# HF_LPF.net
KiCad netlist of a schematic drawn in Altium Designer
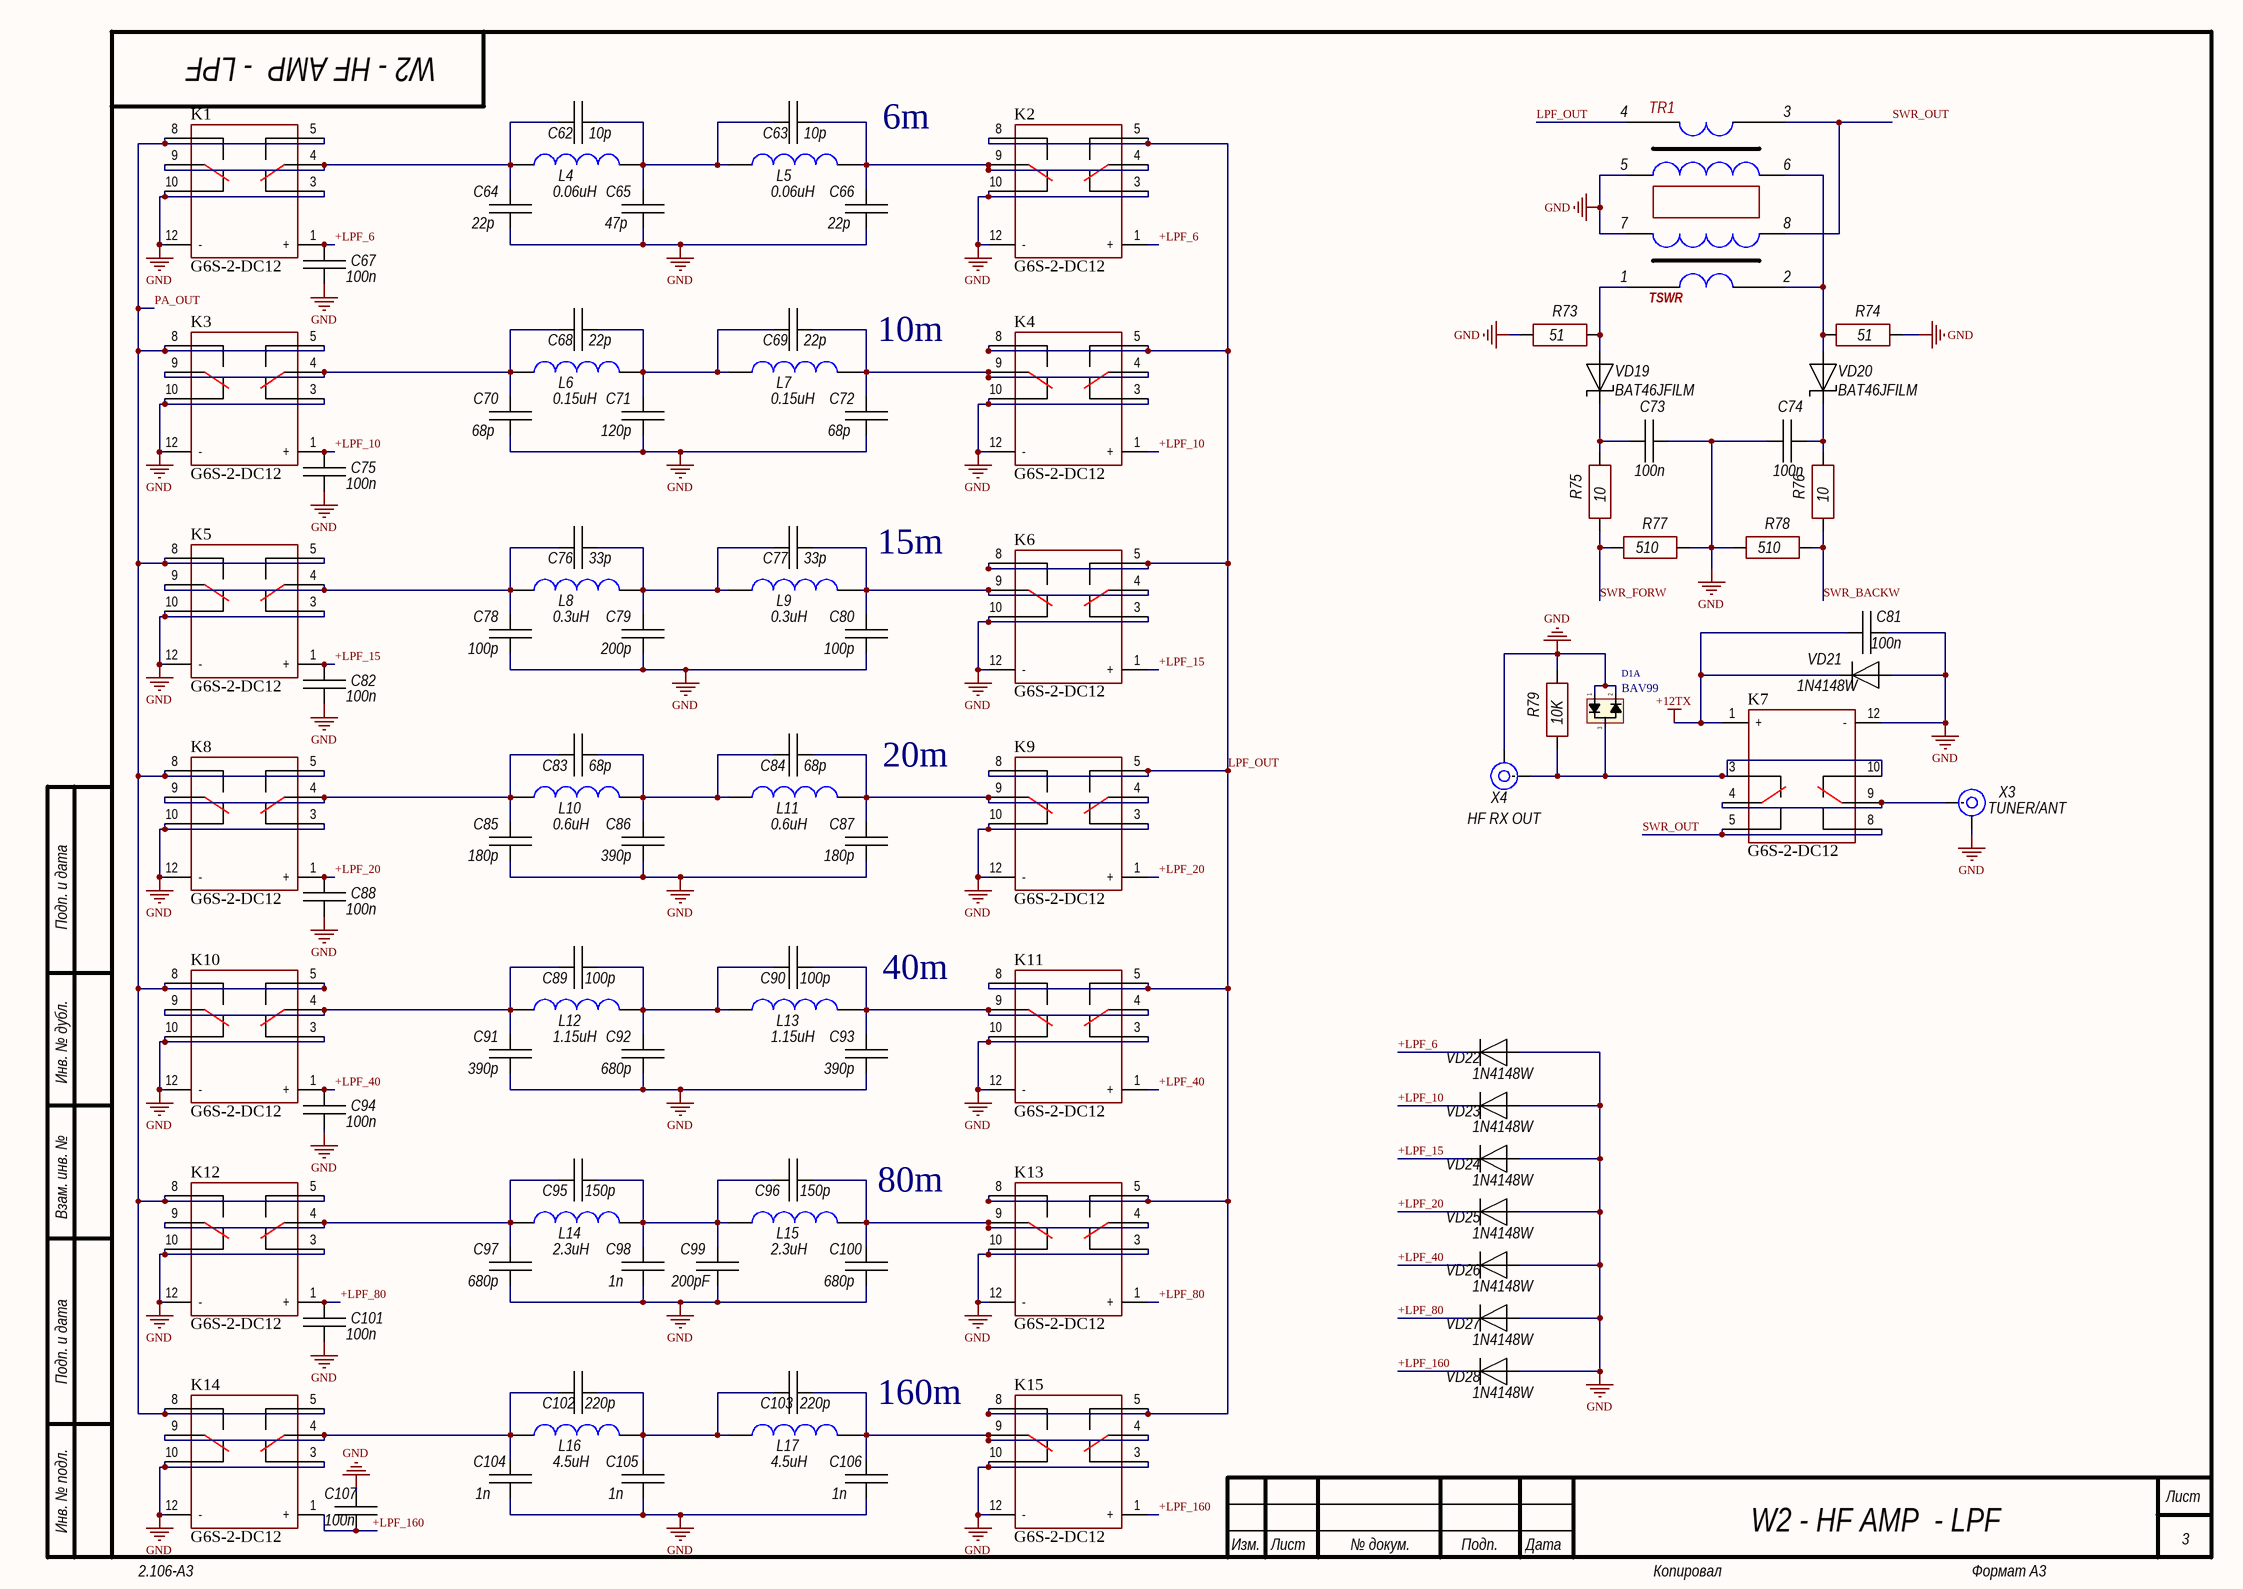
[diagram p0: HF_LPF.SchDoc]

(export (version "E")
  (design (tool "Eeschema 10.0.6"))
  (components
    (comp (ref "C62") (value "10p") (footprint "CH1206ATC") (libsource (lib "Discrete") (part "Capacitor")))
    (comp (ref "C63") (value "10p") (footprint "CH1206ATC") (libsource (lib "Discrete") (part "Capacitor")))
    (comp (ref "C64") (value "22p") (footprint "CH1206ATC") (libsource (lib "Discrete") (part "Capacitor")))
    (comp (ref "C65") (value "47p") (footprint "CH1206ATC") (libsource (lib "Discrete") (part "Capacitor")))
    (comp (ref "C66") (value "22p") (footprint "CH1206ATC") (libsource (lib "Discrete") (part "Capacitor")))
    (comp (ref "C67")
      (value "100n")
      (footprint "standard:CH0805C")
      (libsource (lib "Discrete") (part "Capacitor"))
    )
    (comp (ref "C68") (value "22p") (footprint "CH1206ATC") (libsource (lib "Discrete") (part "Capacitor")))
    (comp (ref "C69") (value "22p") (footprint "CH1206ATC") (libsource (lib "Discrete") (part "Capacitor")))
    (comp (ref "C70") (value "68p") (footprint "CH1206ATC") (libsource (lib "Discrete") (part "Capacitor")))
    (comp (ref "C71") (value "120p") (footprint "CH1206ATC") (libsource (lib "Discrete") (part "Capacitor")))
    (comp (ref "C72") (value "68p") (footprint "CH1206ATC") (libsource (lib "Discrete") (part "Capacitor")))
    (comp (ref "C73")
      (value "100n")
      (footprint "standard:CH1206C")
      (libsource (lib "Discrete") (part "Capacitor"))
    )
    (comp (ref "C74")
      (value "100n")
      (footprint "standard:CH1206C")
      (libsource (lib "Discrete") (part "Capacitor"))
    )
    (comp (ref "C75")
      (value "100n")
      (footprint "standard:CH0805C")
      (libsource (lib "Discrete") (part "Capacitor"))
    )
    (comp (ref "C76") (value "33p") (footprint "CH1206ATC") (libsource (lib "Discrete") (part "Capacitor")))
    (comp (ref "C77") (value "33p") (footprint "CH1206ATC") (libsource (lib "Discrete") (part "Capacitor")))
    (comp (ref "C78") (value "100p") (footprint "CH1206ATC") (libsource (lib "Discrete") (part "Capacitor")))
    (comp (ref "C79") (value "200p") (footprint "CH1206ATC") (libsource (lib "Discrete") (part "Capacitor")))
    (comp (ref "C80") (value "100p") (footprint "CH1206ATC") (libsource (lib "Discrete") (part "Capacitor")))
    (comp (ref "C81")
      (value "100n")
      (footprint "standard:CH1206C")
      (libsource (lib "Discrete") (part "Capacitor"))
    )
    (comp (ref "C82")
      (value "100n")
      (footprint "standard:CH0805C")
      (libsource (lib "Discrete") (part "Capacitor"))
    )
    (comp (ref "C83") (value "68p") (footprint "CH1206ATC") (libsource (lib "Discrete") (part "Capacitor")))
    (comp (ref "C84") (value "68p") (footprint "CH1206ATC") (libsource (lib "Discrete") (part "Capacitor")))
    (comp (ref "C85") (value "180p") (footprint "CH1206ATC") (libsource (lib "Discrete") (part "Capacitor")))
    (comp (ref "C86") (value "390p") (footprint "CH1206ATC") (libsource (lib "Discrete") (part "Capacitor")))
    (comp (ref "C87") (value "180p") (footprint "CH1206ATC") (libsource (lib "Discrete") (part "Capacitor")))
    (comp (ref "C88")
      (value "100n")
      (footprint "standard:CH0805C")
      (libsource (lib "Discrete") (part "Capacitor"))
    )
    (comp (ref "C89") (value "100p") (footprint "CH1206ATC") (libsource (lib "Discrete") (part "Capacitor")))
    (comp (ref "C90") (value "100p") (footprint "CH1206ATC") (libsource (lib "Discrete") (part "Capacitor")))
    (comp (ref "C91") (value "390p") (footprint "CH1206ATC") (libsource (lib "Discrete") (part "Capacitor")))
    (comp (ref "C92") (value "680p") (footprint "CH1206ATC") (libsource (lib "Discrete") (part "Capacitor")))
    (comp (ref "C93") (value "390p") (footprint "CH1206ATC") (libsource (lib "Discrete") (part "Capacitor")))
    (comp (ref "C94")
      (value "100n")
      (footprint "standard:CH0805C")
      (libsource (lib "Discrete") (part "Capacitor"))
    )
    (comp (ref "C95") (value "150p") (footprint "CH1206ATC") (libsource (lib "Discrete") (part "Capacitor")))
    (comp (ref "C96") (value "150p") (footprint "CH1206ATC") (libsource (lib "Discrete") (part "Capacitor")))
    (comp (ref "C97") (value "680p") (footprint "CH1206ATC") (libsource (lib "Discrete") (part "Capacitor")))
    (comp (ref "C98") (value "1n") (footprint "CH1206ATC") (libsource (lib "Discrete") (part "Capacitor")))
    (comp (ref "C99") (value "200pF") (footprint "CH1206ATC") (libsource (lib "Discrete") (part "Capacitor")))
    (comp (ref "C100") (value "680p") (footprint "CH1206ATC") (libsource (lib "Discrete") (part "Capacitor")))
    (comp (ref "C101")
      (value "100n")
      (footprint "standard:CH0805C")
      (libsource (lib "Discrete") (part "Capacitor"))
    )
    (comp (ref "C102") (value "220p") (footprint "CH1206ATC") (libsource (lib "Discrete") (part "Capacitor")))
    (comp (ref "C103") (value "220p") (footprint "CH1206ATC") (libsource (lib "Discrete") (part "Capacitor")))
    (comp (ref "C104") (value "1n") (footprint "CH1206ATC") (libsource (lib "Discrete") (part "Capacitor")))
    (comp (ref "C105") (value "1n") (footprint "CH1206ATC") (libsource (lib "Discrete") (part "Capacitor")))
    (comp (ref "C106") (value "1n") (footprint "CH1206ATC") (libsource (lib "Discrete") (part "Capacitor")))
    (comp (ref "C107")
      (value "100n")
      (footprint "standard:CH0805C")
      (libsource (lib "Discrete") (part "Capacitor"))
    )
    (comp (ref "D1") (value "BAV99") (footprint "SOT23_132") (libsource (lib "Analog") (part "BAV99")))
    (comp (ref "K1")
      (value "G6S-2-DC12")
      (footprint "G6S-2-DC12")
      (libsource (lib "Relay") (part "G6S-2-DC12V_2"))
    )
    (comp (ref "K2")
      (value "G6S-2-DC12")
      (footprint "G6S-2-DC12")
      (libsource (lib "Relay") (part "G6S-2-DC12V_2"))
    )
    (comp (ref "K3")
      (value "G6S-2-DC12")
      (footprint "G6S-2-DC12")
      (libsource (lib "Relay") (part "G6S-2-DC12V_2"))
    )
    (comp (ref "K4")
      (value "G6S-2-DC12")
      (footprint "G6S-2-DC12")
      (libsource (lib "Relay") (part "G6S-2-DC12V_2"))
    )
    (comp (ref "K5")
      (value "G6S-2-DC12")
      (footprint "G6S-2-DC12")
      (libsource (lib "Relay") (part "G6S-2-DC12V_2"))
    )
    (comp (ref "K6")
      (value "G6S-2-DC12")
      (footprint "G6S-2-DC12")
      (libsource (lib "Relay") (part "G6S-2-DC12V_2"))
    )
    (comp (ref "K7")
      (value "G6S-2-DC12")
      (footprint "G6S-2-DC12")
      (libsource (lib "") (part "G6S-2-DC12V_2_1"))
    )
    (comp (ref "K8")
      (value "G6S-2-DC12")
      (footprint "G6S-2-DC12")
      (libsource (lib "Relay") (part "G6S-2-DC12V_2"))
    )
    (comp (ref "K9")
      (value "G6S-2-DC12")
      (footprint "G6S-2-DC12")
      (libsource (lib "Relay") (part "G6S-2-DC12V_2"))
    )
    (comp (ref "K10")
      (value "G6S-2-DC12")
      (footprint "G6S-2-DC12")
      (libsource (lib "Relay") (part "G6S-2-DC12V_2"))
    )
    (comp (ref "K11")
      (value "G6S-2-DC12")
      (footprint "G6S-2-DC12")
      (libsource (lib "Relay") (part "G6S-2-DC12V_2"))
    )
    (comp (ref "K12")
      (value "G6S-2-DC12")
      (footprint "G6S-2-DC12")
      (libsource (lib "Relay") (part "G6S-2-DC12V_2"))
    )
    (comp (ref "K13")
      (value "G6S-2-DC12")
      (footprint "G6S-2-DC12")
      (libsource (lib "Relay") (part "G6S-2-DC12V_2"))
    )
    (comp (ref "K14")
      (value "G6S-2-DC12")
      (footprint "G6S-2-DC12")
      (libsource (lib "Relay") (part "G6S-2-DC12V_2"))
    )
    (comp (ref "K15")
      (value "G6S-2-DC12")
      (footprint "G6S-2-DC12")
      (libsource (lib "Relay") (part "G6S-2-DC12V_2"))
    )
    (comp (ref "L4")
      (value "0.06uH")
      (footprint "DR1")
      (libsource (lib "Transformers") (part "Inductor ring"))
    )
    (comp (ref "L5")
      (value "0.06uH")
      (footprint "DR1")
      (libsource (lib "Transformers") (part "Inductor ring"))
    )
    (comp (ref "L6")
      (value "0.15uH")
      (footprint "DR1")
      (libsource (lib "Transformers") (part "Inductor ring"))
    )
    (comp (ref "L7")
      (value "0.15uH")
      (footprint "DR1")
      (libsource (lib "Transformers") (part "Inductor ring"))
    )
    (comp (ref "L8")
      (value "0.3uH")
      (footprint "T68-0")
      (libsource (lib "Transformers") (part "Inductor ring"))
    )
    (comp (ref "L9")
      (value "0.3uH")
      (footprint "T68-0")
      (libsource (lib "Transformers") (part "Inductor ring"))
    )
    (comp (ref "L10")
      (value "0.6uH")
      (footprint "T68-0")
      (libsource (lib "Transformers") (part "Inductor ring"))
    )
    (comp (ref "L11")
      (value "0.6uH")
      (footprint "T68-0")
      (libsource (lib "Transformers") (part "Inductor ring"))
    )
    (comp (ref "L12")
      (value "1.15uH")
      (footprint "T68-0")
      (libsource (lib "Transformers") (part "Inductor ring"))
    )
    (comp (ref "L13")
      (value "1.15uH")
      (footprint "T68-0")
      (libsource (lib "Transformers") (part "Inductor ring"))
    )
    (comp (ref "L14")
      (value "2.3uH")
      (footprint "T68-0")
      (libsource (lib "Transformers") (part "Inductor ring"))
    )
    (comp (ref "L15")
      (value "2.3uH")
      (footprint "T68-0")
      (libsource (lib "Transformers") (part "Inductor ring"))
    )
    (comp (ref "L16")
      (value "4.5uH")
      (footprint "T68-0")
      (libsource (lib "Transformers") (part "Inductor ring"))
    )
    (comp (ref "L17")
      (value "4.5uH")
      (footprint "T68-0")
      (libsource (lib "Transformers") (part "Inductor ring"))
    )
    (comp (ref "R73")
      (value "51")
      (footprint "standard:CH1206R")
      (libsource (lib "Discrete") (part "Resistor"))
    )
    (comp (ref "R74")
      (value "51")
      (footprint "standard:CH1206R")
      (libsource (lib "Discrete") (part "Resistor"))
    )
    (comp (ref "R75") (value "10") (footprint "standard:CH0805R") (libsource (lib "") (part "Resistor_1")))
    (comp (ref "R76") (value "10") (footprint "standard:CH0805R") (libsource (lib "") (part "Resistor_1")))
    (comp (ref "R77")
      (value "510")
      (footprint "standard:CH0805R")
      (libsource (lib "Discrete") (part "Resistor"))
    )
    (comp (ref "R78")
      (value "510")
      (footprint "standard:CH0805R")
      (libsource (lib "Discrete") (part "Resistor"))
    )
    (comp (ref "R79") (value "10K") (footprint "standard:CH2512R") (libsource (lib "") (part "Resistor_1")))
    (comp (ref "TR1") (value "TSWR") (footprint "TANDEM") (libsource (lib "Transformers") (part "BN43-302")))
    (comp (ref "VD19")
      (value "BAT46JFILM")
      (footprint "standard:SOD323")
      (libsource (lib "Diods") (part "Diod Schottky"))
    )
    (comp (ref "VD20")
      (value "BAT46JFILM")
      (footprint "standard:SOD323")
      (libsource (lib "Diods") (part "Diod Schottky"))
    )
    (comp (ref "VD21")
      (value "1N4148W")
      (footprint "standard:SOD123")
      (libsource (lib "Diods") (part "Diod"))
    )
    (comp (ref "VD22")
      (value "1N4148W")
      (footprint "standard:SOD123")
      (libsource (lib "Diods") (part "Diod"))
    )
    (comp (ref "VD23")
      (value "1N4148W")
      (footprint "standard:SOD123")
      (libsource (lib "Diods") (part "Diod"))
    )
    (comp (ref "VD24")
      (value "1N4148W")
      (footprint "standard:SOD123")
      (libsource (lib "Diods") (part "Diod"))
    )
    (comp (ref "VD25")
      (value "1N4148W")
      (footprint "standard:SOD123")
      (libsource (lib "Diods") (part "Diod"))
    )
    (comp (ref "VD26")
      (value "1N4148W")
      (footprint "standard:SOD123")
      (libsource (lib "Diods") (part "Diod"))
    )
    (comp (ref "VD27")
      (value "1N4148W")
      (footprint "standard:SOD123")
      (libsource (lib "Diods") (part "Diod"))
    )
    (comp (ref "VD28")
      (value "1N4148W")
      (footprint "standard:SOD123")
      (libsource (lib "Diods") (part "Diod"))
    )
    (comp (ref "X3")
      (value "TUNER/ANT")
      (footprint "custom:CON: SMA")
      (description "RF")
      (libsource (lib "Connectors") (part "SMA"))
    )
    (comp (ref "X4")
      (value "HF RX OUT")
      (footprint "custom:CON: SMA")
      (description "RF")
      (libsource (lib "Connectors") (part "SMA"))
    )
  )
  (nets
    (net (code "1") (name "+12TX") (class "Default")
      (node (ref "C81") (pin "1") (pinfunction "1_1") (pintype "power_in"))
      (node (ref "K7") (pin "1") (pinfunction "+_1") (pintype "passive"))
      (node (ref "VD21") (pin "2") (pinfunction "2_2") (pintype "passive"))
    )
    (net (code "2") (name "/+LPF_6") (class "Default")
      (node (ref "C67") (pin "1") (pinfunction "1_1") (pintype "power_in"))
      (node (ref "K1") (pin "1") (pinfunction "+_1") (pintype "passive"))
      (node (ref "K2") (pin "1") (pinfunction "+_1") (pintype "passive"))
      (node (ref "VD22") (pin "2") (pinfunction "2_2") (pintype "passive"))
    )
    (net (code "3") (name "/+LPF_10") (class "Default")
      (node (ref "C75") (pin "1") (pinfunction "1_1") (pintype "power_in"))
      (node (ref "K3") (pin "1") (pinfunction "+_1") (pintype "passive"))
      (node (ref "K4") (pin "1") (pinfunction "+_1") (pintype "passive"))
      (node (ref "VD23") (pin "2") (pinfunction "2_2") (pintype "passive"))
    )
    (net (code "4") (name "/+LPF_15") (class "Default")
      (node (ref "C82") (pin "1") (pinfunction "1_1") (pintype "power_in"))
      (node (ref "K5") (pin "1") (pinfunction "+_1") (pintype "passive"))
      (node (ref "K6") (pin "1") (pinfunction "+_1") (pintype "passive"))
      (node (ref "VD24") (pin "2") (pinfunction "2_2") (pintype "passive"))
    )
    (net (code "5") (name "/+LPF_20") (class "Default")
      (node (ref "C88") (pin "1") (pinfunction "1_1") (pintype "power_in"))
      (node (ref "K8") (pin "1") (pinfunction "+_1") (pintype "passive"))
      (node (ref "K9") (pin "1") (pinfunction "+_1") (pintype "passive"))
      (node (ref "VD25") (pin "2") (pinfunction "2_2") (pintype "passive"))
    )
    (net (code "6") (name "/+LPF_40") (class "Default")
      (node (ref "C94") (pin "1") (pinfunction "1_1") (pintype "power_in"))
      (node (ref "K10") (pin "1") (pinfunction "+_1") (pintype "passive"))
      (node (ref "K11") (pin "1") (pinfunction "+_1") (pintype "passive"))
      (node (ref "VD26") (pin "2") (pinfunction "2_2") (pintype "passive"))
    )
    (net (code "7") (name "/+LPF_80") (class "Default")
      (node (ref "C101") (pin "1") (pinfunction "1_1") (pintype "power_in"))
      (node (ref "K12") (pin "1") (pinfunction "+_1") (pintype "passive"))
      (node (ref "K13") (pin "1") (pinfunction "+_1") (pintype "passive"))
      (node (ref "VD27") (pin "2") (pinfunction "2_2") (pintype "passive"))
    )
    (net (code "8") (name "/+LPF_160") (class "Default")
      (node (ref "C107") (pin "2") (pinfunction "2_2") (pintype "power_in"))
      (node (ref "K14") (pin "1") (pinfunction "+_1") (pintype "passive"))
      (node (ref "K15") (pin "1") (pinfunction "+_1") (pintype "passive"))
      (node (ref "VD28") (pin "2") (pinfunction "2_2") (pintype "passive"))
    )
    (net (code "9") (name "/LPF_OUT") (class "Default")
      (node (ref "K11") (pin "5") (pinfunction "NO_1_5") (pintype "passive"))
      (node (ref "K11") (pin "8") (pinfunction "NO_2_8") (pintype "passive"))
      (node (ref "K13") (pin "5") (pinfunction "NO_1_5") (pintype "passive"))
      (node (ref "K13") (pin "8") (pinfunction "NO_2_8") (pintype "passive"))
      (node (ref "K15") (pin "5") (pinfunction "NO_1_5") (pintype "passive"))
      (node (ref "K15") (pin "8") (pinfunction "NO_2_8") (pintype "passive"))
      (node (ref "K2") (pin "5") (pinfunction "NO_1_5") (pintype "passive"))
      (node (ref "K2") (pin "8") (pinfunction "NO_2_8") (pintype "passive"))
      (node (ref "K4") (pin "5") (pinfunction "NO_1_5") (pintype "passive"))
      (node (ref "K4") (pin "8") (pinfunction "NO_2_8") (pintype "passive"))
      (node (ref "K6") (pin "5") (pinfunction "NO_1_5") (pintype "passive"))
      (node (ref "K6") (pin "8") (pinfunction "NO_2_8") (pintype "passive"))
      (node (ref "K9") (pin "5") (pinfunction "NO_1_5") (pintype "passive"))
      (node (ref "K9") (pin "8") (pinfunction "NO_2_8") (pintype "passive"))
      (node (ref "TR1") (pin "4") (pinfunction "4_4") (pintype "power_in"))
    )
    (net (code "10") (name "/PA_OUT") (class "Default")
      (node (ref "K1") (pin "5") (pinfunction "NO_1_5") (pintype "passive"))
      (node (ref "K1") (pin "8") (pinfunction "NO_2_8") (pintype "passive"))
      (node (ref "K10") (pin "5") (pinfunction "NO_1_5") (pintype "passive"))
      (node (ref "K10") (pin "8") (pinfunction "NO_2_8") (pintype "passive"))
      (node (ref "K12") (pin "5") (pinfunction "NO_1_5") (pintype "passive"))
      (node (ref "K12") (pin "8") (pinfunction "NO_2_8") (pintype "passive"))
      (node (ref "K14") (pin "5") (pinfunction "NO_1_5") (pintype "passive"))
      (node (ref "K14") (pin "8") (pinfunction "NO_2_8") (pintype "passive"))
      (node (ref "K3") (pin "5") (pinfunction "NO_1_5") (pintype "passive"))
      (node (ref "K3") (pin "8") (pinfunction "NO_2_8") (pintype "passive"))
      (node (ref "K5") (pin "5") (pinfunction "NO_1_5") (pintype "passive"))
      (node (ref "K5") (pin "8") (pinfunction "NO_2_8") (pintype "passive"))
      (node (ref "K8") (pin "5") (pinfunction "NO_1_5") (pintype "passive"))
      (node (ref "K8") (pin "8") (pinfunction "NO_2_8") (pintype "passive"))
    )
    (net (code "11") (name "/SWR_BACKW") (class "Default")
      (node (ref "R76") (pin "1") (pinfunction "1_1") (pintype "passive"))
      (node (ref "R78") (pin "2") (pinfunction "2_2") (pintype "passive"))
    )
    (net (code "12") (name "/SWR_FORW") (class "Default")
      (node (ref "R75") (pin "1") (pinfunction "1_1") (pintype "passive"))
      (node (ref "R77") (pin "1") (pinfunction "1_1") (pintype "passive"))
    )
    (net (code "13") (name "/SWR_OUT") (class "Default")
      (node (ref "K7") (pin "5") (pinfunction "NO_1_5") (pintype "passive"))
      (node (ref "K7") (pin "8") (pinfunction "NO_2_8") (pintype "passive"))
      (node (ref "TR1") (pin "3") (pinfunction "3_3") (pintype "power_in"))
      (node (ref "TR1") (pin "8") (pinfunction "8_8") (pintype "power_in"))
    )
    (net (code "14") (name "GND") (class "Default")
      (node (ref "C100") (pin "1") (pinfunction "1_1") (pintype "power_in"))
      (node (ref "C101") (pin "2") (pinfunction "2_2") (pintype "power_in"))
      (node (ref "C104") (pin "1") (pinfunction "1_1") (pintype "power_in"))
      (node (ref "C105") (pin "1") (pinfunction "1_1") (pintype "power_in"))
      (node (ref "C106") (pin "1") (pinfunction "1_1") (pintype "power_in"))
      (node (ref "C107") (pin "1") (pinfunction "1_1") (pintype "power_in"))
      (node (ref "C64") (pin "1") (pinfunction "1_1") (pintype "power_in"))
      (node (ref "C65") (pin "1") (pinfunction "1_1") (pintype "power_in"))
      (node (ref "C66") (pin "1") (pinfunction "1_1") (pintype "power_in"))
      (node (ref "C67") (pin "2") (pinfunction "2_2") (pintype "power_in"))
      (node (ref "C70") (pin "1") (pinfunction "1_1") (pintype "power_in"))
      (node (ref "C71") (pin "1") (pinfunction "1_1") (pintype "power_in"))
      (node (ref "C72") (pin "1") (pinfunction "1_1") (pintype "power_in"))
      (node (ref "C73") (pin "2") (pinfunction "2_2") (pintype "power_in"))
      (node (ref "C74") (pin "1") (pinfunction "1_1") (pintype "power_in"))
      (node (ref "C75") (pin "2") (pinfunction "2_2") (pintype "power_in"))
      (node (ref "C78") (pin "1") (pinfunction "1_1") (pintype "power_in"))
      (node (ref "C79") (pin "1") (pinfunction "1_1") (pintype "power_in"))
      (node (ref "C80") (pin "1") (pinfunction "1_1") (pintype "power_in"))
      (node (ref "C81") (pin "2") (pinfunction "2_2") (pintype "power_in"))
      (node (ref "C82") (pin "2") (pinfunction "2_2") (pintype "power_in"))
      (node (ref "C85") (pin "1") (pinfunction "1_1") (pintype "power_in"))
      (node (ref "C86") (pin "1") (pinfunction "1_1") (pintype "power_in"))
      (node (ref "C87") (pin "1") (pinfunction "1_1") (pintype "power_in"))
      (node (ref "C88") (pin "2") (pinfunction "2_2") (pintype "power_in"))
      (node (ref "C91") (pin "1") (pinfunction "1_1") (pintype "power_in"))
      (node (ref "C92") (pin "1") (pinfunction "1_1") (pintype "power_in"))
      (node (ref "C93") (pin "1") (pinfunction "1_1") (pintype "power_in"))
      (node (ref "C94") (pin "2") (pinfunction "2_2") (pintype "power_in"))
      (node (ref "C97") (pin "1") (pinfunction "1_1") (pintype "power_in"))
      (node (ref "C98") (pin "1") (pinfunction "1_1") (pintype "power_in"))
      (node (ref "C99") (pin "1") (pinfunction "1_1") (pintype "power_in"))
      (node (ref "D1") (pin "1") (pinfunction "11_1") (pintype "passive"))
      (node (ref "D1") (pin "2") (pinfunction "10_2") (pintype "passive"))
      (node (ref "K1") (pin "10") (pinfunction "NC_2_10") (pintype "passive"))
      (node (ref "K1") (pin "12") (pinfunction "-_12") (pintype "passive"))
      (node (ref "K1") (pin "3") (pinfunction "NC_1_3") (pintype "passive"))
      (node (ref "K10") (pin "10") (pinfunction "NC_2_10") (pintype "passive"))
      (node (ref "K10") (pin "12") (pinfunction "-_12") (pintype "passive"))
      (node (ref "K10") (pin "3") (pinfunction "NC_1_3") (pintype "passive"))
      (node (ref "K11") (pin "10") (pinfunction "NC_2_10") (pintype "passive"))
      (node (ref "K11") (pin "12") (pinfunction "-_12") (pintype "passive"))
      (node (ref "K11") (pin "3") (pinfunction "NC_1_3") (pintype "passive"))
      (node (ref "K12") (pin "10") (pinfunction "NC_2_10") (pintype "passive"))
      (node (ref "K12") (pin "12") (pinfunction "-_12") (pintype "passive"))
      (node (ref "K12") (pin "3") (pinfunction "NC_1_3") (pintype "passive"))
      (node (ref "K13") (pin "10") (pinfunction "NC_2_10") (pintype "passive"))
      (node (ref "K13") (pin "12") (pinfunction "-_12") (pintype "passive"))
      (node (ref "K13") (pin "3") (pinfunction "NC_1_3") (pintype "passive"))
      (node (ref "K14") (pin "10") (pinfunction "NC_2_10") (pintype "passive"))
      (node (ref "K14") (pin "12") (pinfunction "-_12") (pintype "passive"))
      (node (ref "K14") (pin "3") (pinfunction "NC_1_3") (pintype "passive"))
      (node (ref "K15") (pin "10") (pinfunction "NC_2_10") (pintype "passive"))
      (node (ref "K15") (pin "12") (pinfunction "-_12") (pintype "passive"))
      (node (ref "K15") (pin "3") (pinfunction "NC_1_3") (pintype "passive"))
      (node (ref "K2") (pin "10") (pinfunction "NC_2_10") (pintype "passive"))
      (node (ref "K2") (pin "12") (pinfunction "-_12") (pintype "passive"))
      (node (ref "K2") (pin "3") (pinfunction "NC_1_3") (pintype "passive"))
      (node (ref "K3") (pin "10") (pinfunction "NC_2_10") (pintype "passive"))
      (node (ref "K3") (pin "12") (pinfunction "-_12") (pintype "passive"))
      (node (ref "K3") (pin "3") (pinfunction "NC_1_3") (pintype "passive"))
      (node (ref "K4") (pin "10") (pinfunction "NC_2_10") (pintype "passive"))
      (node (ref "K4") (pin "12") (pinfunction "-_12") (pintype "passive"))
      (node (ref "K4") (pin "3") (pinfunction "NC_1_3") (pintype "passive"))
      (node (ref "K5") (pin "10") (pinfunction "NC_2_10") (pintype "passive"))
      (node (ref "K5") (pin "12") (pinfunction "-_12") (pintype "passive"))
      (node (ref "K5") (pin "3") (pinfunction "NC_1_3") (pintype "passive"))
      (node (ref "K6") (pin "10") (pinfunction "NC_2_10") (pintype "passive"))
      (node (ref "K6") (pin "12") (pinfunction "-_12") (pintype "passive"))
      (node (ref "K6") (pin "3") (pinfunction "NC_1_3") (pintype "passive"))
      (node (ref "K7") (pin "12") (pinfunction "-_12") (pintype "passive"))
      (node (ref "K8") (pin "10") (pinfunction "NC_2_10") (pintype "passive"))
      (node (ref "K8") (pin "12") (pinfunction "-_12") (pintype "passive"))
      (node (ref "K8") (pin "3") (pinfunction "NC_1_3") (pintype "passive"))
      (node (ref "K9") (pin "10") (pinfunction "NC_2_10") (pintype "passive"))
      (node (ref "K9") (pin "12") (pinfunction "-_12") (pintype "passive"))
      (node (ref "K9") (pin "3") (pinfunction "NC_1_3") (pintype "passive"))
      (node (ref "R73") (pin "1") (pinfunction "1_1") (pintype "passive"))
      (node (ref "R74") (pin "2") (pinfunction "2_2") (pintype "passive"))
      (node (ref "R77") (pin "2") (pinfunction "2_2") (pintype "passive"))
      (node (ref "R78") (pin "1") (pinfunction "1_1") (pintype "passive"))
      (node (ref "R79") (pin "2") (pinfunction "2_2") (pintype "passive"))
      (node (ref "TR1") (pin "5") (pinfunction "5_5") (pintype "power_in"))
      (node (ref "TR1") (pin "7") (pinfunction "8_7") (pintype "power_in"))
      (node (ref "VD21") (pin "1") (pinfunction "1_1") (pintype "passive"))
      (node (ref "VD22") (pin "1") (pinfunction "1_1") (pintype "passive"))
      (node (ref "VD23") (pin "1") (pinfunction "1_1") (pintype "passive"))
      (node (ref "VD24") (pin "1") (pinfunction "1_1") (pintype "passive"))
      (node (ref "VD25") (pin "1") (pinfunction "1_1") (pintype "passive"))
      (node (ref "VD26") (pin "1") (pinfunction "1_1") (pintype "passive"))
      (node (ref "VD27") (pin "1") (pinfunction "1_1") (pintype "passive"))
      (node (ref "VD28") (pin "1") (pinfunction "1_1") (pintype "passive"))
      (node (ref "X3") (pin "2") (pinfunction "IN_2") (pintype "passive"))
      (node (ref "X4") (pin "2") (pinfunction "IN_2") (pintype "passive"))
    )
    (net (code "15") (name "Net-(C62-Pad1)") (class "Default")
      (node (ref "C62") (pin "1") (pinfunction "1_1") (pintype "power_in"))
      (node (ref "C63") (pin "2") (pinfunction "2_2") (pintype "power_in"))
      (node (ref "C65") (pin "2") (pinfunction "2_2") (pintype "power_in"))
      (node (ref "L4") (pin "1") (pinfunction "1_1") (pintype "passive"))
      (node (ref "L5") (pin "2") (pinfunction "2_2") (pintype "passive"))
    )
    (net (code "16") (name "Net-(C68-Pad1)") (class "Default")
      (node (ref "C68") (pin "1") (pinfunction "1_1") (pintype "power_in"))
      (node (ref "C69") (pin "2") (pinfunction "2_2") (pintype "power_in"))
      (node (ref "C71") (pin "2") (pinfunction "2_2") (pintype "power_in"))
      (node (ref "L6") (pin "1") (pinfunction "1_1") (pintype "passive"))
      (node (ref "L7") (pin "2") (pinfunction "2_2") (pintype "passive"))
    )
    (net (code "17") (name "Net-(C73-Pad1)") (class "Default")
      (node (ref "C73") (pin "1") (pinfunction "1_1") (pintype "power_in"))
      (node (ref "R75") (pin "2") (pinfunction "2_2") (pintype "passive"))
      (node (ref "VD19") (pin "2") (pinfunction "2_2") (pintype "passive"))
    )
    (net (code "18") (name "Net-(C74-Pad2)") (class "Default")
      (node (ref "C74") (pin "2") (pinfunction "2_2") (pintype "power_in"))
      (node (ref "R76") (pin "2") (pinfunction "2_2") (pintype "passive"))
      (node (ref "VD20") (pin "2") (pinfunction "2_2") (pintype "passive"))
    )
    (net (code "19") (name "Net-(C76-Pad1)") (class "Default")
      (node (ref "C76") (pin "1") (pinfunction "1_1") (pintype "power_in"))
      (node (ref "C77") (pin "2") (pinfunction "2_2") (pintype "power_in"))
      (node (ref "C79") (pin "2") (pinfunction "2_2") (pintype "power_in"))
      (node (ref "L8") (pin "1") (pinfunction "1_1") (pintype "passive"))
      (node (ref "L9") (pin "2") (pinfunction "2_2") (pintype "passive"))
    )
    (net (code "20") (name "Net-(C83-Pad1)") (class "Default")
      (node (ref "C83") (pin "1") (pinfunction "1_1") (pintype "power_in"))
      (node (ref "C84") (pin "2") (pinfunction "2_2") (pintype "power_in"))
      (node (ref "C86") (pin "2") (pinfunction "2_2") (pintype "power_in"))
      (node (ref "L10") (pin "1") (pinfunction "1_1") (pintype "passive"))
      (node (ref "L11") (pin "2") (pinfunction "2_2") (pintype "passive"))
    )
    (net (code "21") (name "Net-(C89-Pad1)") (class "Default")
      (node (ref "C89") (pin "1") (pinfunction "1_1") (pintype "power_in"))
      (node (ref "C90") (pin "2") (pinfunction "2_2") (pintype "power_in"))
      (node (ref "C92") (pin "2") (pinfunction "2_2") (pintype "power_in"))
      (node (ref "L12") (pin "1") (pinfunction "1_1") (pintype "passive"))
      (node (ref "L13") (pin "2") (pinfunction "2_2") (pintype "passive"))
    )
    (net (code "22") (name "Net-(C95-Pad1)") (class "Default")
      (node (ref "C95") (pin "1") (pinfunction "1_1") (pintype "power_in"))
      (node (ref "C96") (pin "2") (pinfunction "2_2") (pintype "power_in"))
      (node (ref "C98") (pin "2") (pinfunction "2_2") (pintype "power_in"))
      (node (ref "C99") (pin "2") (pinfunction "2_2") (pintype "power_in"))
      (node (ref "L14") (pin "1") (pinfunction "1_1") (pintype "passive"))
      (node (ref "L15") (pin "2") (pinfunction "2_2") (pintype "passive"))
    )
    (net (code "23") (name "Net-(C102-Pad1)") (class "Default")
      (node (ref "C102") (pin "1") (pinfunction "1_1") (pintype "power_in"))
      (node (ref "C103") (pin "2") (pinfunction "2_2") (pintype "power_in"))
      (node (ref "C105") (pin "2") (pinfunction "2_2") (pintype "power_in"))
      (node (ref "L16") (pin "1") (pinfunction "1_1") (pintype "passive"))
      (node (ref "L17") (pin "2") (pinfunction "2_2") (pintype "passive"))
    )
    (net (code "24") (name "Net-(D1A-9)") (class "Default")
      (node (ref "D1") (pin "3") (pinfunction "9_3") (pintype "passive"))
      (node (ref "K7") (pin "10") (pinfunction "NC_2_10") (pintype "passive"))
      (node (ref "K7") (pin "3") (pinfunction "NC_1_3") (pintype "passive"))
      (node (ref "R79") (pin "1") (pinfunction "1_1") (pintype "passive"))
      (node (ref "X4") (pin "1") (pinfunction "IN_1") (pintype "passive"))
    )
    (net (code "25") (name "Net-(K1-COM_1)") (class "Default")
      (node (ref "C62") (pin "2") (pinfunction "2_2") (pintype "power_in"))
      (node (ref "C64") (pin "2") (pinfunction "2_2") (pintype "power_in"))
      (node (ref "K1") (pin "4") (pinfunction "COM_1_4") (pintype "passive"))
      (node (ref "K1") (pin "9") (pinfunction "COM_2_9") (pintype "passive"))
      (node (ref "L4") (pin "2") (pinfunction "2_2") (pintype "passive"))
    )
    (net (code "26") (name "Net-(K2-COM_1)") (class "Default")
      (node (ref "C63") (pin "1") (pinfunction "1_1") (pintype "power_in"))
      (node (ref "C66") (pin "2") (pinfunction "2_2") (pintype "power_in"))
      (node (ref "K2") (pin "4") (pinfunction "COM_1_4") (pintype "passive"))
      (node (ref "K2") (pin "9") (pinfunction "COM_2_9") (pintype "passive"))
      (node (ref "L5") (pin "1") (pinfunction "1_1") (pintype "passive"))
    )
    (net (code "27") (name "Net-(K3-COM_1)") (class "Default")
      (node (ref "C68") (pin "2") (pinfunction "2_2") (pintype "power_in"))
      (node (ref "C70") (pin "2") (pinfunction "2_2") (pintype "power_in"))
      (node (ref "K3") (pin "4") (pinfunction "COM_1_4") (pintype "passive"))
      (node (ref "K3") (pin "9") (pinfunction "COM_2_9") (pintype "passive"))
      (node (ref "L6") (pin "2") (pinfunction "2_2") (pintype "passive"))
    )
    (net (code "28") (name "Net-(K4-COM_1)") (class "Default")
      (node (ref "C69") (pin "1") (pinfunction "1_1") (pintype "power_in"))
      (node (ref "C72") (pin "2") (pinfunction "2_2") (pintype "power_in"))
      (node (ref "K4") (pin "4") (pinfunction "COM_1_4") (pintype "passive"))
      (node (ref "K4") (pin "9") (pinfunction "COM_2_9") (pintype "passive"))
      (node (ref "L7") (pin "1") (pinfunction "1_1") (pintype "passive"))
    )
    (net (code "29") (name "Net-(K5-COM_1)") (class "Default")
      (node (ref "C76") (pin "2") (pinfunction "2_2") (pintype "power_in"))
      (node (ref "C78") (pin "2") (pinfunction "2_2") (pintype "power_in"))
      (node (ref "K5") (pin "4") (pinfunction "COM_1_4") (pintype "passive"))
      (node (ref "K5") (pin "9") (pinfunction "COM_2_9") (pintype "passive"))
      (node (ref "L8") (pin "2") (pinfunction "2_2") (pintype "passive"))
    )
    (net (code "30") (name "Net-(K6-COM_1)") (class "Default")
      (node (ref "C77") (pin "1") (pinfunction "1_1") (pintype "power_in"))
      (node (ref "C80") (pin "2") (pinfunction "2_2") (pintype "power_in"))
      (node (ref "K6") (pin "4") (pinfunction "COM_1_4") (pintype "passive"))
      (node (ref "K6") (pin "9") (pinfunction "COM_2_9") (pintype "passive"))
      (node (ref "L9") (pin "1") (pinfunction "1_1") (pintype "passive"))
    )
    (net (code "31") (name "Net-(K7-COM_1)") (class "Default")
      (node (ref "K7") (pin "4") (pinfunction "COM_1_4") (pintype "passive"))
      (node (ref "K7") (pin "9") (pinfunction "COM_2_9") (pintype "passive"))
      (node (ref "X3") (pin "1") (pinfunction "IN_1") (pintype "passive"))
    )
    (net (code "32") (name "Net-(K8-COM_1)") (class "Default")
      (node (ref "C83") (pin "2") (pinfunction "2_2") (pintype "power_in"))
      (node (ref "C85") (pin "2") (pinfunction "2_2") (pintype "power_in"))
      (node (ref "K8") (pin "4") (pinfunction "COM_1_4") (pintype "passive"))
      (node (ref "K8") (pin "9") (pinfunction "COM_2_9") (pintype "passive"))
      (node (ref "L10") (pin "2") (pinfunction "2_2") (pintype "passive"))
    )
    (net (code "33") (name "Net-(K9-COM_1)") (class "Default")
      (node (ref "C84") (pin "1") (pinfunction "1_1") (pintype "power_in"))
      (node (ref "C87") (pin "2") (pinfunction "2_2") (pintype "power_in"))
      (node (ref "K9") (pin "4") (pinfunction "COM_1_4") (pintype "passive"))
      (node (ref "K9") (pin "9") (pinfunction "COM_2_9") (pintype "passive"))
      (node (ref "L11") (pin "1") (pinfunction "1_1") (pintype "passive"))
    )
    (net (code "34") (name "Net-(K10-COM_1)") (class "Default")
      (node (ref "C89") (pin "2") (pinfunction "2_2") (pintype "power_in"))
      (node (ref "C91") (pin "2") (pinfunction "2_2") (pintype "power_in"))
      (node (ref "K10") (pin "4") (pinfunction "COM_1_4") (pintype "passive"))
      (node (ref "K10") (pin "9") (pinfunction "COM_2_9") (pintype "passive"))
      (node (ref "L12") (pin "2") (pinfunction "2_2") (pintype "passive"))
    )
    (net (code "35") (name "Net-(K11-COM_1)") (class "Default")
      (node (ref "C90") (pin "1") (pinfunction "1_1") (pintype "power_in"))
      (node (ref "C93") (pin "2") (pinfunction "2_2") (pintype "power_in"))
      (node (ref "K11") (pin "4") (pinfunction "COM_1_4") (pintype "passive"))
      (node (ref "K11") (pin "9") (pinfunction "COM_2_9") (pintype "passive"))
      (node (ref "L13") (pin "1") (pinfunction "1_1") (pintype "passive"))
    )
    (net (code "36") (name "Net-(K12-COM_1)") (class "Default")
      (node (ref "C95") (pin "2") (pinfunction "2_2") (pintype "power_in"))
      (node (ref "C97") (pin "2") (pinfunction "2_2") (pintype "power_in"))
      (node (ref "K12") (pin "4") (pinfunction "COM_1_4") (pintype "passive"))
      (node (ref "K12") (pin "9") (pinfunction "COM_2_9") (pintype "passive"))
      (node (ref "L14") (pin "2") (pinfunction "2_2") (pintype "passive"))
    )
    (net (code "37") (name "Net-(K13-COM_1)") (class "Default")
      (node (ref "C100") (pin "2") (pinfunction "2_2") (pintype "power_in"))
      (node (ref "C96") (pin "1") (pinfunction "1_1") (pintype "power_in"))
      (node (ref "K13") (pin "4") (pinfunction "COM_1_4") (pintype "passive"))
      (node (ref "K13") (pin "9") (pinfunction "COM_2_9") (pintype "passive"))
      (node (ref "L15") (pin "1") (pinfunction "1_1") (pintype "passive"))
    )
    (net (code "38") (name "Net-(K14-COM_1)") (class "Default")
      (node (ref "C102") (pin "2") (pinfunction "2_2") (pintype "power_in"))
      (node (ref "C104") (pin "2") (pinfunction "2_2") (pintype "power_in"))
      (node (ref "K14") (pin "4") (pinfunction "COM_1_4") (pintype "passive"))
      (node (ref "K14") (pin "9") (pinfunction "COM_2_9") (pintype "passive"))
      (node (ref "L16") (pin "2") (pinfunction "2_2") (pintype "passive"))
    )
    (net (code "39") (name "Net-(K15-COM_1)") (class "Default")
      (node (ref "C103") (pin "1") (pinfunction "1_1") (pintype "power_in"))
      (node (ref "C106") (pin "2") (pinfunction "2_2") (pintype "power_in"))
      (node (ref "K15") (pin "4") (pinfunction "COM_1_4") (pintype "passive"))
      (node (ref "K15") (pin "9") (pinfunction "COM_2_9") (pintype "passive"))
      (node (ref "L17") (pin "1") (pinfunction "1_1") (pintype "passive"))
    )
    (net (code "40") (name "Net-(R73-Pad2)") (class "Default")
      (node (ref "R73") (pin "2") (pinfunction "2_2") (pintype "passive"))
      (node (ref "TR1") (pin "1") (pinfunction "1_1") (pintype "power_in"))
      (node (ref "VD19") (pin "1") (pinfunction "1_1") (pintype "passive"))
    )
    (net (code "41") (name "Net-(R74-Pad1)") (class "Default")
      (node (ref "R74") (pin "1") (pinfunction "1_1") (pintype "passive"))
      (node (ref "TR1") (pin "2") (pinfunction "2_2") (pintype "power_in"))
      (node (ref "TR1") (pin "6") (pinfunction "6_6") (pintype "power_in"))
      (node (ref "VD20") (pin "1") (pinfunction "1_1") (pintype "passive"))
    )
  )
)
